# Sheet2.net
KiCad netlist of a schematic drawn in Altium Designer
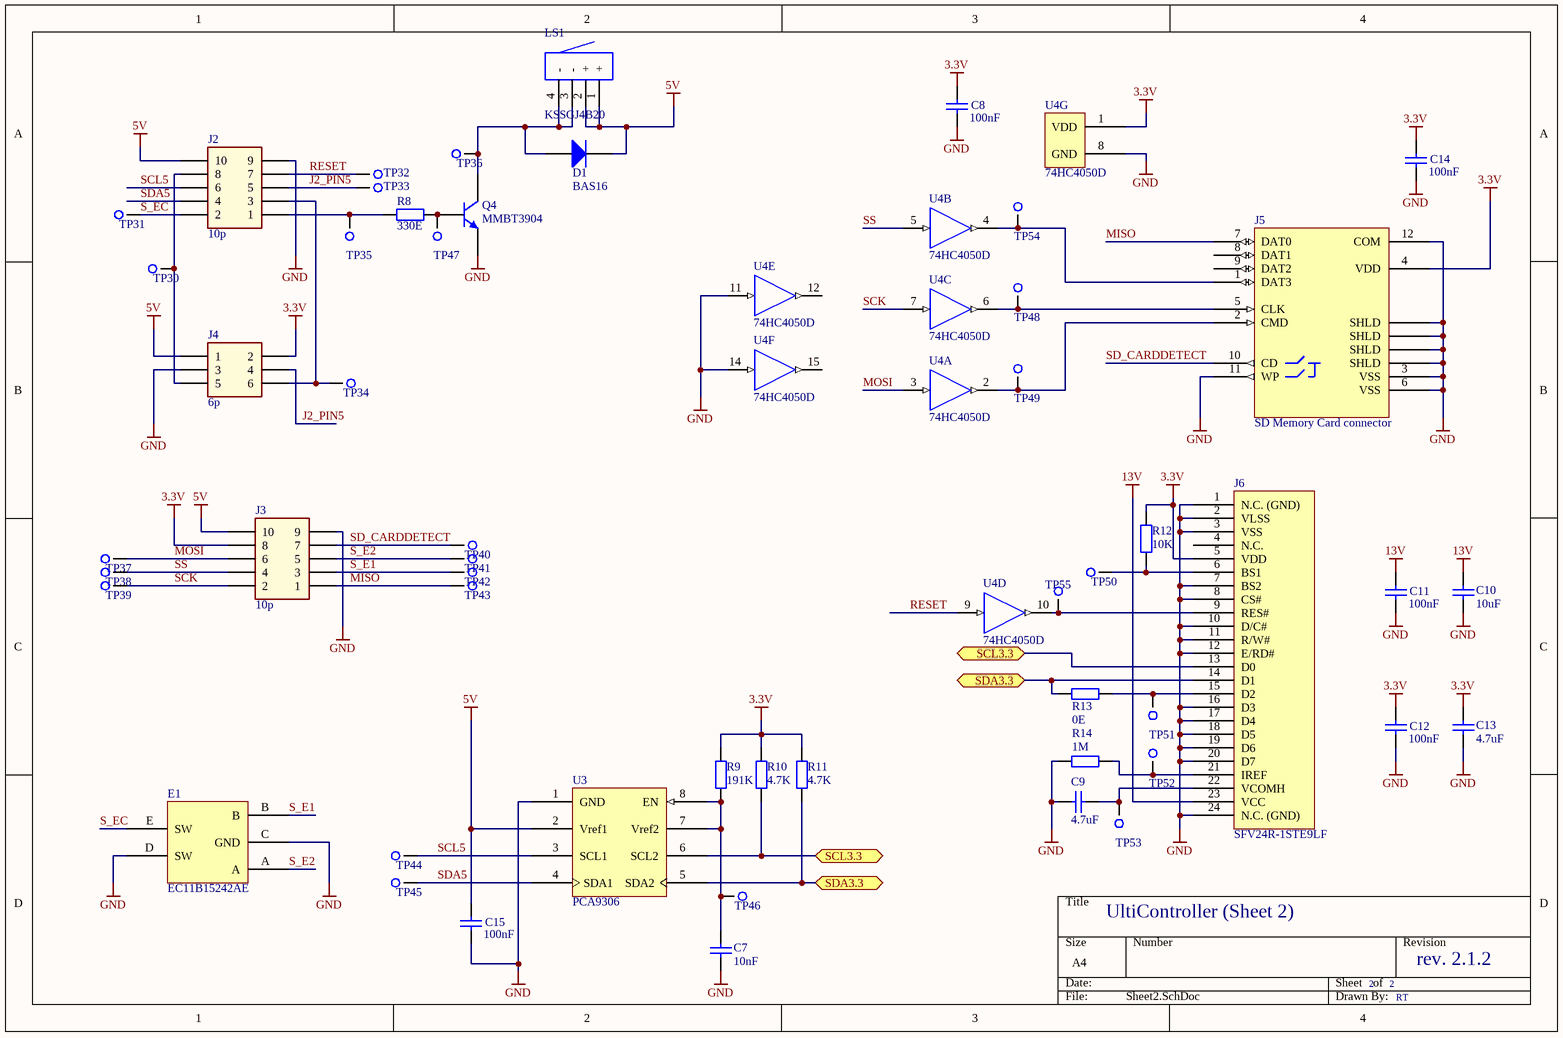
[diagram p0: Sheet2.SchDoc]

(export (version "E")
  (design (tool "Eeschema 10.0.6"))
  (components
    (comp (ref "C7")
      (value "10nF")
      (footprint "C0805 (2012)")
      (description "Cap 10nF X7R 0805 10% 100V")
      (fields (field (name "MFG") "AVX"))
      (libsource (lib "Faber_SCH_lib") (part "Cap 10nF X7R 0805"))
    )
    (comp (ref "C8")
      (value "100nF")
      (footprint "C0805 (2012)")
      (description "Cap 100nF X7R 0805 10% 100V")
      (fields (field (name "MFG") "AVX"))
      (libsource (lib "Faber_SCH_lib") (part "Cap 100nF X7R 0805"))
    )
    (comp (ref "C9")
      (value "4.7uF")
      (footprint "C1206 (3216)")
      (description "Cap 4.7uF 1206 X7R 10% 25V")
      (fields (field (name "MFG") "TDK"))
      (libsource (lib "Faber_SCH_lib") (part "Cap 4.7uF X7R 1206"))
    )
    (comp (ref "C10")
      (value "10uF")
      (footprint "C1206 (3216)")
      (description "Cap 10uF 1206 X7R 10% 25V")
      (fields (field (name "MFG") "KEMET"))
      (libsource (lib "Faber_SCH_lib") (part "Cap 10uF X7R 1206"))
    )
    (comp (ref "C11")
      (value "100nF")
      (footprint "C0805 (2012)")
      (description "Cap 100nF X7R 0805 10% 100V")
      (fields (field (name "MFG") "AVX"))
      (libsource (lib "Faber_SCH_lib") (part "Cap 100nF X7R 0805"))
    )
    (comp (ref "C12")
      (value "100nF")
      (footprint "C0805 (2012)")
      (description "Cap 100nF X7R 0805 10% 100V")
      (fields (field (name "MFG") "AVX"))
      (libsource (lib "Faber_SCH_lib") (part "Cap 100nF X7R 0805"))
    )
    (comp (ref "C13")
      (value "4.7uF")
      (footprint "C1206 (3216)")
      (description "Cap 4.7uF 1206 X7R 10% 25V")
      (fields (field (name "MFG") "TDK"))
      (libsource (lib "Faber_SCH_lib") (part "Cap 4.7uF X7R 1206"))
    )
    (comp (ref "C14")
      (value "100nF")
      (footprint "C0805 (2012)")
      (description "Cap 100nF X7R 0805 10% 100V")
      (fields (field (name "MFG") "AVX"))
      (libsource (lib "Faber_SCH_lib") (part "Cap 100nF X7R 0805"))
    )
    (comp (ref "C15")
      (value "100nF")
      (footprint "C0805 (2012)")
      (description "Cap 100nF X7R 0805 10% 100V")
      (fields (field (name "MFG") "AVX"))
      (libsource (lib "Faber_SCH_lib") (part "Cap 100nF X7R 0805"))
    )
    (comp (ref "D1")
      (value "BAS16")
      (footprint "IC SOT23")
      (description "Diode BAS16  SOT23 85V 215MA")
      (fields (field (name "MFG") "NXP"))
      (libsource (lib "Faber_SCH_lib") (part "Diode BAS16"))
    )
    (comp (ref "E1")
      (value "EC11B15242AE")
      (footprint "Misc EC11B15242AE")
      (description "Misc EC11B15242AE encoder horiz")
      (fields (field (name "MFG") "ALPS"))
      (libsource (lib "Faber_SCH_lib") (part "Misc EC11B15242AE"))
    )
    (comp (ref "J2")
      (value "10p")
      (footprint "HEADER 10P right angle")
      (description "Header 2x5p right angle 2.54mm")
      (fields (field (name "MFG") "WURTH ELEKTRONIK"))
      (libsource (lib "Faber_SCH_lib") (part "Header 10p"))
    )
    (comp (ref "J3")
      (value "10p")
      (footprint "HEADER 10P right angle")
      (description "Header 2x5p right angle 2.54mm")
      (fields (field (name "MFG") "WURTH ELEKTRONIK"))
      (libsource (lib "Faber_SCH_lib") (part "Header 10p"))
    )
    (comp (ref "J4")
      (value "6p")
      (footprint "HEADER 6P RIGHT ANGLE")
      (description "Header 2x3p right angle 2.54mm")
      (fields (field (name "MFG") "FCI"))
      (libsource (lib "Faber_SCH_lib") (part "Header 6p r.a."))
    )
    (comp (ref "J5")
      (value "SD Memory Card connector")
      (footprint "CON SD-Card")
      (description "Connector Std,reverse SD Memory Card connector")
      (fields (field (name "MFG") "HRS (HIROSE)"))
      (libsource (lib "Faber_SCH_lib") (part "Connector SD-Card-Hirose"))
    )
    (comp (ref "J6")
      (value "SFV24R-1STE9LF")
      (footprint "Con SFV24R-1STE9LF")
      (description "Connector FPC/FFC 0.5mm R/A 24p SMD")
      (fields (field (name "MFG") "FCI"))
      (libsource (lib "Faber_SCH_lib") (part "Connector SFV24R-1STE9LF"))
    )
    (comp (ref "LS1")
      (value "KSSGJ4B20")
      (footprint "Buzzer KSSGJ4B20")
      (description "Buzzer KSSGJ4B20 SMD")
      (fields (field (name "MFG") "KINGSTATE"))
      (libsource (lib "Faber_SCH_lib") (part "Buzzer KSSGJ4B20"))
    )
    (comp (ref "Q4")
      (value "MMBT3904")
      (footprint "IC SOT23")
      (description "NPN MMBT3904 SOT-23 200mA")
      (fields (field (name "MFG") "NXP"))
      (libsource (lib "Faber_SCH_lib") (part "NPN MMBT3904"))
    )
    (comp (ref "R8")
      (value "330E")
      (footprint "R0805 (2012)")
      (description "Res 330E 0805 1% 100mW")
      (fields (field (name "MFG") "MULTICOMP"))
      (libsource (lib "Faber_SCH_lib") (part "Res 330E 0805"))
    )
    (comp (ref "R9")
      (value "191K")
      (footprint "R0805 (2012)")
      (description "Res 191K 0805 1% 125mW")
      (fields (field (name "MFG") "VISHAY DRALORIC"))
      (libsource (lib "Faber_SCH_lib") (part "Res 191K 0805"))
    )
    (comp (ref "R10")
      (value "4.7K")
      (footprint "R0805 (2012)")
      (description "Res 4.7K 0805 1% 100mW")
      (fields (field (name "MFG") "MULTICOMP"))
      (libsource (lib "Faber_SCH_lib") (part "Res 4.7K 0805"))
    )
    (comp (ref "R11")
      (value "4.7K")
      (footprint "R0805 (2012)")
      (description "Res 4.7K 0805 1% 100mW")
      (fields (field (name "MFG") "MULTICOMP"))
      (libsource (lib "Faber_SCH_lib") (part "Res 4.7K 0805"))
    )
    (comp (ref "R12")
      (value "10K")
      (footprint "R0805 (2012)")
      (description "Res 10K 0805 1% 100mW")
      (fields (field (name "MFG") "MULTICOMP"))
      (libsource (lib "Faber_SCH_lib") (part "Res 10K 0805"))
    )
    (comp (ref "R13")
      (value "0E")
      (footprint "R0805 (2012)")
      (description "Res 0E 0805 1% 100mW")
      (fields (field (name "MFG") "MULTICOMP"))
      (libsource (lib "Faber_SCH_lib") (part "Res 0E 0805"))
    )
    (comp (ref "R14")
      (value "1M")
      (footprint "R0805 (2012)")
      (description "Res 1M 0805 1% 100mW")
      (fields (field (name "MFG") "MULTICOMP"))
      (libsource (lib "Faber_SCH_lib") (part "Res 1M 0805"))
    )
    (comp (ref "TP30")
      (value "2mm")
      (footprint "TESTPOINT 2mm")
      (description "Testpoint, 2mm, round")
      (libsource (lib "Faber_SCH_lib") (part "Testpoint, 2mm, round"))
    )
    (comp (ref "TP31")
      (value "2mm")
      (footprint "TESTPOINT 2mm")
      (description "Testpoint, 2mm, round")
      (libsource (lib "Faber_SCH_lib") (part "Testpoint, 2mm, round"))
    )
    (comp (ref "TP32")
      (value "2mm")
      (footprint "TESTPOINT 2mm")
      (description "Testpoint, 2mm, round")
      (libsource (lib "Faber_SCH_lib") (part "Testpoint, 2mm, round"))
    )
    (comp (ref "TP33")
      (value "2mm")
      (footprint "TESTPOINT 2mm")
      (description "Testpoint, 2mm, round")
      (libsource (lib "Faber_SCH_lib") (part "Testpoint, 2mm, round"))
    )
    (comp (ref "TP34")
      (value "2mm")
      (footprint "TESTPOINT 2mm")
      (description "Testpoint, 2mm, round")
      (libsource (lib "Faber_SCH_lib") (part "Testpoint, 2mm, round"))
    )
    (comp (ref "TP35")
      (value "2mm")
      (footprint "TESTPOINT 2mm")
      (description "Testpoint, 2mm, round")
      (libsource (lib "Faber_SCH_lib") (part "Testpoint, 2mm, round"))
    )
    (comp (ref "TP36")
      (value "2mm")
      (footprint "TESTPOINT 2mm")
      (description "Testpoint, 2mm, round")
      (libsource (lib "Faber_SCH_lib") (part "Testpoint, 2mm, round"))
    )
    (comp (ref "TP37")
      (value "2mm")
      (footprint "TESTPOINT 2mm")
      (description "Testpoint, 2mm, round")
      (libsource (lib "Faber_SCH_lib") (part "Testpoint, 2mm, round"))
    )
    (comp (ref "TP38")
      (value "2mm")
      (footprint "TESTPOINT 2mm")
      (description "Testpoint, 2mm, round")
      (libsource (lib "Faber_SCH_lib") (part "Testpoint, 2mm, round"))
    )
    (comp (ref "TP39")
      (value "2mm")
      (footprint "TESTPOINT 2mm")
      (description "Testpoint, 2mm, round")
      (libsource (lib "Faber_SCH_lib") (part "Testpoint, 2mm, round"))
    )
    (comp (ref "TP40")
      (value "2mm")
      (footprint "TESTPOINT 2mm")
      (description "Testpoint, 2mm, round")
      (libsource (lib "Faber_SCH_lib") (part "Testpoint, 2mm, round"))
    )
    (comp (ref "TP41")
      (value "2mm")
      (footprint "TESTPOINT 2mm")
      (description "Testpoint, 2mm, round")
      (libsource (lib "Faber_SCH_lib") (part "Testpoint, 2mm, round"))
    )
    (comp (ref "TP42")
      (value "2mm")
      (footprint "TESTPOINT 2mm")
      (description "Testpoint, 2mm, round")
      (libsource (lib "Faber_SCH_lib") (part "Testpoint, 2mm, round"))
    )
    (comp (ref "TP43")
      (value "2mm")
      (footprint "TESTPOINT 2mm")
      (description "Testpoint, 2mm, round")
      (libsource (lib "Faber_SCH_lib") (part "Testpoint, 2mm, round"))
    )
    (comp (ref "TP44")
      (value "2mm")
      (footprint "TESTPOINT 2mm")
      (description "Testpoint, 2mm, round")
      (libsource (lib "Faber_SCH_lib") (part "Testpoint, 2mm, round"))
    )
    (comp (ref "TP45")
      (value "2mm")
      (footprint "TESTPOINT 2mm")
      (description "Testpoint, 2mm, round")
      (libsource (lib "Faber_SCH_lib") (part "Testpoint, 2mm, round"))
    )
    (comp (ref "TP46")
      (value "2mm")
      (footprint "TESTPOINT 2mm")
      (description "Testpoint, 2mm, round")
      (libsource (lib "Faber_SCH_lib") (part "Testpoint, 2mm, round"))
    )
    (comp (ref "TP47")
      (value "2mm")
      (footprint "TESTPOINT 2mm")
      (description "Testpoint, 2mm, round")
      (libsource (lib "Faber_SCH_lib") (part "Testpoint, 2mm, round"))
    )
    (comp (ref "TP48")
      (value "2mm")
      (footprint "TESTPOINT 2mm")
      (description "Testpoint, 2mm, round")
      (libsource (lib "Faber_SCH_lib") (part "Testpoint, 2mm, round"))
    )
    (comp (ref "TP49")
      (value "2mm")
      (footprint "TESTPOINT 2mm")
      (description "Testpoint, 2mm, round")
      (libsource (lib "Faber_SCH_lib") (part "Testpoint, 2mm, round"))
    )
    (comp (ref "TP50")
      (value "2mm")
      (footprint "TESTPOINT 2mm")
      (description "Testpoint, 2mm, round")
      (libsource (lib "Faber_SCH_lib") (part "Testpoint, 2mm, round"))
    )
    (comp (ref "TP51")
      (value "2mm")
      (footprint "TESTPOINT 2mm")
      (description "Testpoint, 2mm, round")
      (libsource (lib "Faber_SCH_lib") (part "Testpoint, 2mm, round"))
    )
    (comp (ref "TP52")
      (value "2mm")
      (footprint "TESTPOINT 2mm")
      (description "Testpoint, 2mm, round")
      (libsource (lib "Faber_SCH_lib") (part "Testpoint, 2mm, round"))
    )
    (comp (ref "TP53")
      (value "2mm")
      (footprint "TESTPOINT 2mm")
      (description "Testpoint, 2mm, round")
      (libsource (lib "Faber_SCH_lib") (part "Testpoint, 2mm, round"))
    )
    (comp (ref "TP54")
      (value "2mm")
      (footprint "TESTPOINT 2mm")
      (description "Testpoint, 2mm, round")
      (libsource (lib "Faber_SCH_lib") (part "Testpoint, 2mm, round"))
    )
    (comp (ref "TP55")
      (value "2mm")
      (footprint "TESTPOINT 2mm")
      (description "Testpoint, 2mm, round")
      (libsource (lib "Faber_SCH_lib") (part "Testpoint, 2mm, round"))
    )
    (comp (ref "U3")
      (value "PCA9306")
      (footprint "IC SSOP-8")
      (description "IC PCA9306 Voltage Level translator")
      (fields (field (name "MFG") "TEXAS INSTRUMENTS"))
      (libsource (lib "Faber_SCH_lib") (part "IC PCA9306"))
    )
    (comp (ref "U4")
      (value "74HC4050D")
      (footprint "IC SOIC-16")
      (description "IC Hex Non-Inverting Buffer/Logic-Level Down Converter")
      (fields (field (name "MFG") "NXP"))
      (libsource (lib "Faber_SCH_lib") (part "IC 74HC4050D"))
    )
  )
  (nets
    (net (code "1") (name "/J2_PIN5") (class "Default")
      (node (ref "J2") (pin "5") (pinfunction "5_5") (pintype "passive"))
      (node (ref "J4") (pin "4") (pinfunction "4_4") (pintype "passive"))
      (node (ref "TP33") (pin "1") (pinfunction "1_1") (pintype "passive"))
    )
    (net (code "2") (name "/MISO") (class "Default")
      (node (ref "J3") (pin "1") (pinfunction "1_1") (pintype "passive"))
      (node (ref "J5") (pin "7") (pinfunction "DAT0_7") (pintype "bidirectional"))
      (node (ref "TP43") (pin "1") (pinfunction "1_1") (pintype "passive"))
    )
    (net (code "3") (name "/MOSI") (class "Default")
      (node (ref "J3") (pin "6") (pinfunction "6_6") (pintype "passive"))
      (node (ref "TP37") (pin "1") (pinfunction "1_1") (pintype "passive"))
      (node (ref "U4") (pin "3") (pinfunction "A_3") (pintype "input"))
    )
    (net (code "4") (name "/RESET") (class "Default")
      (node (ref "J2") (pin "7") (pinfunction "7_7") (pintype "passive"))
      (node (ref "TP32") (pin "1") (pinfunction "1_1") (pintype "passive"))
      (node (ref "U4") (pin "9") (pinfunction "A_9") (pintype "input"))
    )
    (net (code "5") (name "/SCK") (class "Default")
      (node (ref "J3") (pin "2") (pinfunction "2_2") (pintype "passive"))
      (node (ref "TP39") (pin "1") (pinfunction "1_1") (pintype "passive"))
      (node (ref "U4") (pin "7") (pinfunction "A_7") (pintype "input"))
    )
    (net (code "6") (name "/SCL3.3") (class "Default")
      (node (ref "J6") (pin "13") (pinfunction "D0_13") (pintype "passive"))
      (node (ref "R10") (pin "1") (pinfunction "1_1") (pintype "passive"))
      (node (ref "U3") (pin "6") (pinfunction "SCL2_6") (pintype "passive"))
    )
    (net (code "7") (name "/SCL5") (class "Default")
      (node (ref "J2") (pin "6") (pinfunction "6_6") (pintype "passive"))
      (node (ref "TP44") (pin "1") (pinfunction "1_1") (pintype "passive"))
      (node (ref "U3") (pin "3") (pinfunction "SCL1_3") (pintype "passive"))
    )
    (net (code "8") (name "/SDA3.3") (class "Default")
      (node (ref "J6") (pin "14") (pinfunction "D1_14") (pintype "passive"))
      (node (ref "R11") (pin "1") (pinfunction "1_1") (pintype "passive"))
      (node (ref "R13") (pin "1") (pinfunction "1_1") (pintype "passive"))
      (node (ref "U3") (pin "5") (pinfunction "SDA2_5") (pintype "passive"))
    )
    (net (code "9") (name "/SDA5") (class "Default")
      (node (ref "J2") (pin "4") (pinfunction "4_4") (pintype "passive"))
      (node (ref "TP45") (pin "1") (pinfunction "1_1") (pintype "passive"))
      (node (ref "U3") (pin "4") (pinfunction "SDA1_4") (pintype "passive"))
    )
    (net (code "10") (name "/SD_CARDDETECT") (class "Default")
      (node (ref "J3") (pin "7") (pinfunction "7_7") (pintype "passive"))
      (node (ref "J5") (pin "10") (pinfunction "CD_10") (pintype "output"))
      (node (ref "TP40") (pin "1") (pinfunction "1_1") (pintype "passive"))
    )
    (net (code "11") (name "/SS") (class "Default")
      (node (ref "J3") (pin "4") (pinfunction "4_4") (pintype "passive"))
      (node (ref "TP38") (pin "1") (pinfunction "1_1") (pintype "passive"))
      (node (ref "U4") (pin "5") (pinfunction "A_5") (pintype "input"))
    )
    (net (code "12") (name "/S_E1") (class "Default")
      (node (ref "E1") (pin "B") (pinfunction "B_B") (pintype "passive"))
      (node (ref "J3") (pin "3") (pinfunction "3_3") (pintype "passive"))
      (node (ref "TP42") (pin "1") (pinfunction "1_1") (pintype "passive"))
    )
    (net (code "13") (name "/S_E2") (class "Default")
      (node (ref "E1") (pin "A") (pinfunction "A_A") (pintype "passive"))
      (node (ref "J3") (pin "5") (pinfunction "5_5") (pintype "passive"))
      (node (ref "TP41") (pin "1") (pinfunction "1_1") (pintype "passive"))
    )
    (net (code "14") (name "/S_EC") (class "Default")
      (node (ref "E1") (pin "E") (pinfunction "SW_E") (pintype "passive"))
      (node (ref "J2") (pin "2") (pinfunction "2_2") (pintype "passive"))
      (node (ref "TP31") (pin "1") (pinfunction "1_1") (pintype "passive"))
    )
    (net (code "15") (name "3.3V") (class "Default")
      (node (ref "C12") (pin "2") (pinfunction "2_2") (pintype "passive"))
      (node (ref "C13") (pin "1") (pinfunction "1_1") (pintype "passive"))
      (node (ref "C14") (pin "2") (pinfunction "2_2") (pintype "passive"))
      (node (ref "C8") (pin "2") (pinfunction "2_2") (pintype "passive"))
      (node (ref "J3") (pin "8") (pinfunction "8_8") (pintype "passive"))
      (node (ref "J4") (pin "2") (pinfunction "2_2") (pintype "passive"))
      (node (ref "J5") (pin "4") (pinfunction "VDD_4") (pintype "power_in"))
      (node (ref "J6") (pin "5") (pinfunction "VDD_5") (pintype "passive"))
      (node (ref "R10") (pin "2") (pinfunction "2_2") (pintype "passive"))
      (node (ref "R11") (pin "2") (pinfunction "2_2") (pintype "passive"))
      (node (ref "R12") (pin "2") (pinfunction "2_2") (pintype "passive"))
      (node (ref "R9") (pin "2") (pinfunction "2_2") (pintype "passive"))
      (node (ref "U4") (pin "1") (pinfunction "VDD_1") (pintype "power_in"))
    )
    (net (code "16") (name "5V") (class "Default")
      (node (ref "C15") (pin "2") (pinfunction "2_2") (pintype "passive"))
      (node (ref "D1") (pin "3") (pinfunction "K_3") (pintype "passive"))
      (node (ref "J2") (pin "10") (pinfunction "10_10") (pintype "passive"))
      (node (ref "J3") (pin "10") (pinfunction "10_10") (pintype "passive"))
      (node (ref "J4") (pin "1") (pinfunction "1_1") (pintype "passive"))
      (node (ref "LS1") (pin "1") (pinfunction "+_1") (pintype "passive"))
      (node (ref "LS1") (pin "2") (pinfunction "+_2") (pintype "passive"))
      (node (ref "U3") (pin "2") (pinfunction "Vref1_2") (pintype "power_in"))
    )
    (net (code "17") (name "13V") (class "Default")
      (node (ref "C10") (pin "2") (pinfunction "2_2") (pintype "passive"))
      (node (ref "C11") (pin "2") (pinfunction "2_2") (pintype "passive"))
      (node (ref "J6") (pin "23") (pinfunction "VCC_23") (pintype "passive"))
    )
    (net (code "18") (name "GND") (class "Default")
      (node (ref "C10") (pin "1") (pinfunction "1_1") (pintype "passive"))
      (node (ref "C11") (pin "1") (pinfunction "1_1") (pintype "passive"))
      (node (ref "C12") (pin "1") (pinfunction "1_1") (pintype "passive"))
      (node (ref "C13") (pin "2") (pinfunction "2_2") (pintype "passive"))
      (node (ref "C14") (pin "1") (pinfunction "1_1") (pintype "passive"))
      (node (ref "C15") (pin "1") (pinfunction "1_1") (pintype "passive"))
      (node (ref "C7") (pin "1") (pinfunction "1_1") (pintype "passive"))
      (node (ref "C8") (pin "1") (pinfunction "1_1") (pintype "passive"))
      (node (ref "C9") (pin "2") (pinfunction "2_2") (pintype "passive"))
      (node (ref "E1") (pin "C") (pinfunction "GND_C") (pintype "passive"))
      (node (ref "E1") (pin "D") (pinfunction "SW_D") (pintype "passive"))
      (node (ref "J2") (pin "9") (pinfunction "9_9") (pintype "passive"))
      (node (ref "J3") (pin "9") (pinfunction "9_9") (pintype "passive"))
      (node (ref "J4") (pin "3") (pinfunction "3_3") (pintype "passive"))
      (node (ref "J5") (pin "11") (pinfunction "WP_11") (pintype "output"))
      (node (ref "J5") (pin "12") (pinfunction "COM_12") (pintype "power_in"))
      (node (ref "J5") (pin "3") (pinfunction "VSS_3") (pintype "power_in"))
      (node (ref "J5") (pin "6") (pinfunction "VSS_6") (pintype "power_in"))
      (node (ref "J5") (pin "A") (pinfunction "SHLD_A") (pintype "power_in"))
      (node (ref "J5") (pin "B") (pinfunction "SHLD_B") (pintype "power_in"))
      (node (ref "J5") (pin "C") (pinfunction "SHLD_C") (pintype "power_in"))
      (node (ref "J5") (pin "D") (pinfunction "SHLD_D") (pintype "power_in"))
      (node (ref "J6") (pin "1") (pinfunction "N.C._(GND)_1") (pintype "passive"))
      (node (ref "J6") (pin "10") (pinfunction "D/C#_10") (pintype "passive"))
      (node (ref "J6") (pin "11") (pinfunction "R/W#_11") (pintype "passive"))
      (node (ref "J6") (pin "12") (pinfunction "E/RD#_12") (pintype "passive"))
      (node (ref "J6") (pin "16") (pinfunction "D3_16") (pintype "passive"))
      (node (ref "J6") (pin "17") (pinfunction "D4_17") (pintype "passive"))
      (node (ref "J6") (pin "18") (pinfunction "D5_18") (pintype "passive"))
      (node (ref "J6") (pin "19") (pinfunction "D6_19") (pintype "passive"))
      (node (ref "J6") (pin "2") (pinfunction "VLSS_2") (pintype "passive"))
      (node (ref "J6") (pin "20") (pinfunction "D7_20") (pintype "passive"))
      (node (ref "J6") (pin "24") (pinfunction "N.C._(GND)_24") (pintype "passive"))
      (node (ref "J6") (pin "3") (pinfunction "VSS_3") (pintype "passive"))
      (node (ref "J6") (pin "7") (pinfunction "BS2_7") (pintype "passive"))
      (node (ref "J6") (pin "8") (pinfunction "CS#_8") (pintype "passive"))
      (node (ref "Q4") (pin "2") (pinfunction "E_2") (pintype "passive"))
      (node (ref "R14") (pin "1") (pinfunction "1_1") (pintype "passive"))
      (node (ref "U3") (pin "1") (pinfunction "GND_1") (pintype "power_in"))
      (node (ref "U4") (pin "11") (pinfunction "A_11") (pintype "input"))
      (node (ref "U4") (pin "14") (pinfunction "A_14") (pintype "input"))
      (node (ref "U4") (pin "8") (pinfunction "GND_8") (pintype "power_in"))
    )
    (net (code "19") (name "Net-(D1-A)") (class "Default")
      (node (ref "D1") (pin "1") (pinfunction "A_1") (pintype "passive"))
      (node (ref "LS1") (pin "3") (pinfunction "-_3") (pintype "passive"))
      (node (ref "LS1") (pin "4") (pinfunction "-_4") (pintype "passive"))
      (node (ref "Q4") (pin "3") (pinfunction "C_3") (pintype "passive"))
      (node (ref "TP36") (pin "1") (pinfunction "1_1") (pintype "passive"))
    )
    (net (code "20") (name "Net-(J2-Pad1)") (class "Default")
      (node (ref "J2") (pin "1") (pinfunction "1_1") (pintype "passive"))
      (node (ref "R8") (pin "1") (pinfunction "1_1") (pintype "passive"))
      (node (ref "TP35") (pin "1") (pinfunction "1_1") (pintype "passive"))
    )
    (net (code "21") (name "Net-(J2-Pad3)") (class "Default")
      (node (ref "J2") (pin "3") (pinfunction "3_3") (pintype "passive"))
      (node (ref "J4") (pin "6") (pinfunction "6_6") (pintype "passive"))
      (node (ref "TP34") (pin "1") (pinfunction "1_1") (pintype "passive"))
    )
    (net (code "22") (name "Net-(J2-Pad8)") (class "Default")
      (node (ref "J2") (pin "8") (pinfunction "8_8") (pintype "passive"))
      (node (ref "J4") (pin "5") (pinfunction "5_5") (pintype "passive"))
      (node (ref "TP30") (pin "1") (pinfunction "1_1") (pintype "passive"))
    )
    (net (code "23") (name "Net-(J5-CLK)") (class "Default")
      (node (ref "J5") (pin "5") (pinfunction "CLK_5") (pintype "input"))
      (node (ref "TP48") (pin "1") (pinfunction "1_1") (pintype "passive"))
      (node (ref "U4") (pin "6") (pinfunction "Y_6") (pintype "output"))
    )
    (net (code "24") (name "Net-(J5-CMD)") (class "Default")
      (node (ref "J5") (pin "2") (pinfunction "CMD_2") (pintype "input"))
      (node (ref "TP49") (pin "1") (pinfunction "1_1") (pintype "passive"))
      (node (ref "U4") (pin "2") (pinfunction "Y_2") (pintype "output"))
    )
    (net (code "25") (name "Net-(J5-DAT3)") (class "Default")
      (node (ref "J5") (pin "1") (pinfunction "DAT3_1") (pintype "bidirectional"))
      (node (ref "TP54") (pin "1") (pinfunction "1_1") (pintype "passive"))
      (node (ref "U4") (pin "4") (pinfunction "Y_4") (pintype "output"))
    )
    (net (code "26") (name "Net-(J6-BS1)") (class "Default")
      (node (ref "J6") (pin "6") (pinfunction "BS1_6") (pintype "passive"))
      (node (ref "R12") (pin "1") (pinfunction "1_1") (pintype "passive"))
      (node (ref "TP50") (pin "1") (pinfunction "1_1") (pintype "passive"))
    )
    (net (code "27") (name "Net-(J6-D2)") (class "Default")
      (node (ref "J6") (pin "15") (pinfunction "D2_15") (pintype "passive"))
      (node (ref "R13") (pin "2") (pinfunction "2_2") (pintype "passive"))
      (node (ref "TP51") (pin "1") (pinfunction "1_1") (pintype "passive"))
    )
    (net (code "28") (name "Net-(J6-IREF)") (class "Default")
      (node (ref "J6") (pin "21") (pinfunction "IREF_21") (pintype "passive"))
      (node (ref "R14") (pin "2") (pinfunction "2_2") (pintype "passive"))
      (node (ref "TP52") (pin "1") (pinfunction "1_1") (pintype "passive"))
    )
    (net (code "29") (name "Net-(J6-RES#)") (class "Default")
      (node (ref "J6") (pin "9") (pinfunction "RES#_9") (pintype "passive"))
      (node (ref "TP55") (pin "1") (pinfunction "1_1") (pintype "passive"))
      (node (ref "U4") (pin "10") (pinfunction "Y_10") (pintype "output"))
    )
    (net (code "30") (name "Net-(J6-VCOMH)") (class "Default")
      (node (ref "C9") (pin "1") (pinfunction "1_1") (pintype "passive"))
      (node (ref "J6") (pin "22") (pinfunction "VCOMH_22") (pintype "passive"))
      (node (ref "TP53") (pin "1") (pinfunction "1_1") (pintype "passive"))
    )
    (net (code "31") (name "Net-(Q4-B)") (class "Default")
      (node (ref "Q4") (pin "1") (pinfunction "B_1") (pintype "passive"))
      (node (ref "R8") (pin "2") (pinfunction "2_2") (pintype "passive"))
      (node (ref "TP47") (pin "1") (pinfunction "1_1") (pintype "passive"))
    )
    (net (code "32") (name "Net-(U3-EN)") (class "Default")
      (node (ref "C7") (pin "2") (pinfunction "2_2") (pintype "passive"))
      (node (ref "R9") (pin "1") (pinfunction "1_1") (pintype "passive"))
      (node (ref "TP46") (pin "1") (pinfunction "1_1") (pintype "passive"))
      (node (ref "U3") (pin "7") (pinfunction "Vref2_7") (pintype "power_in"))
      (node (ref "U3") (pin "8") (pinfunction "EN_8") (pintype "input"))
    )
    (net (code "33") (name "unconnected-(J5-DAT1-Pad8)") (class "Default")
      (node (ref "J5") (pin "8") (pinfunction "DAT1_8") (pintype "bidirectional"))
    )
    (net (code "34") (name "unconnected-(J5-DAT2-Pad9)") (class "Default")
      (node (ref "J5") (pin "9") (pinfunction "DAT2_9") (pintype "bidirectional"))
    )
    (net (code "35") (name "unconnected-(J6-N.C.-Pad4)") (class "Default")
      (node (ref "J6") (pin "4") (pinfunction "N.C._4") (pintype "passive"))
    )
    (net (code "36") (name "unconnected-(U4E-Y-Pad12)") (class "Default")
      (node (ref "U4") (pin "12") (pinfunction "Y_12") (pintype "output"))
    )
    (net (code "37") (name "unconnected-(U4F-Y-Pad15)") (class "Default")
      (node (ref "U4") (pin "15") (pinfunction "Y_15") (pintype "output"))
    )
  )
)
